# Top.net
KiCad netlist of a schematic drawn in Altium Designer
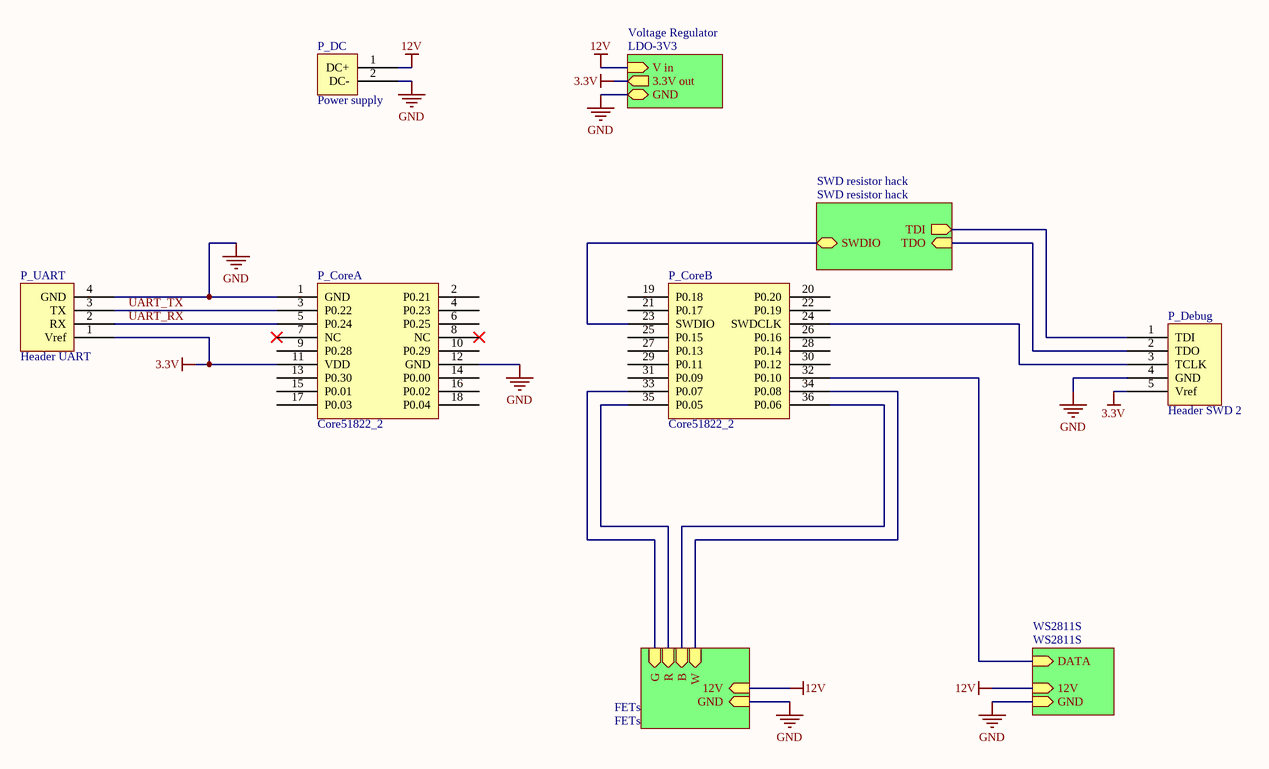
[diagram p0: Top.SchDoc]

(export (version "E")
  (design (tool "Eeschema 10.0.6"))
  (components
    (comp (ref "P_Core")
      (value "Core51822_2")
      (footprint "Core51822")
      (libsource (lib "Modules") (part "Core51822_2"))
    )
    (comp (ref "P_DC")
      (value "Power supply")
      (footprint "DC cable pad with holes")
      (libsource (lib "Core51822-related") (part "Power supply"))
    )
    (comp (ref "P_Debug")
      (value "Header SWD 2")
      (footprint "Header 1x5 2.54mm")
      (libsource (lib "Headers") (part "Header SWD 2"))
    )
    (comp (ref "P_UART")
      (value "Header UART")
      (footprint "Header 1x4 2.54mm")
      (libsource (lib "Core51822-related") (part "Header UART"))
    )
  )
  (nets
    (net (code "1") (name "/B") (class "Default")
      (node (ref "P_Core") (pin "36") (pinfunction "P0.06_36") (pintype "passive"))
    )
    (net (code "2") (name "/DATA") (class "Default")
      (node (ref "P_Core") (pin "32") (pinfunction "P0.10_32") (pintype "passive"))
    )
    (net (code "3") (name "/G") (class "Default")
      (node (ref "P_Core") (pin "33") (pinfunction "P0.07_33") (pintype "passive"))
    )
    (net (code "4") (name "/R") (class "Default")
      (node (ref "P_Core") (pin "35") (pinfunction "P0.05_35") (pintype "passive"))
    )
    (net (code "5") (name "/SWDIO") (class "Default")
      (node (ref "P_Core") (pin "23") (pinfunction "SWDIO_23") (pintype "passive"))
    )
    (net (code "6") (name "/TDI") (class "Default")
      (node (ref "P_Debug") (pin "1") (pinfunction "TDI_1") (pintype "passive"))
    )
    (net (code "7") (name "/TDO") (class "Default")
      (node (ref "P_Debug") (pin "2") (pinfunction "TDO_2") (pintype "passive"))
    )
    (net (code "8") (name "/UART_RX") (class "Default")
      (node (ref "P_Core") (pin "5") (pinfunction "P0.24_5") (pintype "passive"))
      (node (ref "P_UART") (pin "2") (pinfunction "RX_2") (pintype "passive"))
    )
    (net (code "9") (name "/UART_TX") (class "Default")
      (node (ref "P_Core") (pin "3") (pinfunction "P0.22_3") (pintype "power_in"))
      (node (ref "P_UART") (pin "3") (pinfunction "TX_3") (pintype "passive"))
    )
    (net (code "10") (name "/W") (class "Default")
      (node (ref "P_Core") (pin "34") (pinfunction "P0.08_34") (pintype "passive"))
    )
    (net (code "11") (name "3.3V") (class "Default")
      (node (ref "P_Core") (pin "11") (pinfunction "VDD_11") (pintype "passive"))
      (node (ref "P_Debug") (pin "5") (pinfunction "Vref_5") (pintype "passive"))
      (node (ref "P_UART") (pin "1") (pinfunction "Vref_1") (pintype "passive"))
    )
    (net (code "12") (name "12V") (class "Default")
      (node (ref "P_DC") (pin "1") (pinfunction "DC+_1") (pintype "passive"))
    )
    (net (code "13") (name "GND") (class "Default")
      (node (ref "P_Core") (pin "1") (pinfunction "GND_1") (pintype "passive"))
      (node (ref "P_Core") (pin "12") (pinfunction "GND_12") (pintype "passive"))
      (node (ref "P_DC") (pin "2") (pinfunction "DC-_2") (pintype "passive"))
      (node (ref "P_Debug") (pin "4") (pinfunction "GND_4") (pintype "passive"))
      (node (ref "P_UART") (pin "4") (pinfunction "GND_4") (pintype "passive"))
    )
    (net (code "14") (name "Net-(P_CoreB-SWDCLK)") (class "Default")
      (node (ref "P_Core") (pin "24") (pinfunction "SWDCLK_24") (pintype "passive"))
      (node (ref "P_Debug") (pin "3") (pinfunction "TCLK_3") (pintype "passive"))
    )
    (net (code "15") (name "unconnected-(P_CoreA-NC-Pad7)") (class "Default")
      (node (ref "P_Core") (pin "7") (pinfunction "NC_7") (pintype "passive+no_connect"))
    )
    (net (code "16") (name "unconnected-(P_CoreA-NC-Pad8)") (class "Default")
      (node (ref "P_Core") (pin "8") (pinfunction "NC_8") (pintype "passive+no_connect"))
    )
    (net (code "17") (name "unconnected-(P_CoreA-P0.00-Pad14)") (class "Default")
      (node (ref "P_Core") (pin "14") (pinfunction "P0.00_14") (pintype "passive"))
    )
    (net (code "18") (name "unconnected-(P_CoreA-P0.01-Pad15)") (class "Default")
      (node (ref "P_Core") (pin "15") (pinfunction "P0.01_15") (pintype "passive"))
    )
    (net (code "19") (name "unconnected-(P_CoreA-P0.02-Pad16)") (class "Default")
      (node (ref "P_Core") (pin "16") (pinfunction "P0.02_16") (pintype "passive"))
    )
    (net (code "20") (name "unconnected-(P_CoreA-P0.03-Pad17)") (class "Default")
      (node (ref "P_Core") (pin "17") (pinfunction "P0.03_17") (pintype "passive"))
    )
    (net (code "21") (name "unconnected-(P_CoreA-P0.04-Pad18)") (class "Default")
      (node (ref "P_Core") (pin "18") (pinfunction "P0.04_18") (pintype "passive"))
    )
    (net (code "22") (name "unconnected-(P_CoreA-P0.21-Pad2)") (class "Default")
      (node (ref "P_Core") (pin "2") (pinfunction "P0.21_2") (pintype "passive"))
    )
    (net (code "23") (name "unconnected-(P_CoreA-P0.23-Pad4)") (class "Default")
      (node (ref "P_Core") (pin "4") (pinfunction "P0.23_4") (pintype "passive"))
    )
    (net (code "24") (name "unconnected-(P_CoreA-P0.25-Pad6)") (class "Default")
      (node (ref "P_Core") (pin "6") (pinfunction "P0.25_6") (pintype "passive"))
    )
    (net (code "25") (name "unconnected-(P_CoreA-P0.28-Pad9)") (class "Default")
      (node (ref "P_Core") (pin "9") (pinfunction "P0.28_9") (pintype "passive"))
    )
    (net (code "26") (name "unconnected-(P_CoreA-P0.29-Pad10)") (class "Default")
      (node (ref "P_Core") (pin "10") (pinfunction "P0.29_10") (pintype "passive"))
    )
    (net (code "27") (name "unconnected-(P_CoreA-P0.30-Pad13)") (class "Default")
      (node (ref "P_Core") (pin "13") (pinfunction "P0.30_13") (pintype "passive"))
    )
    (net (code "28") (name "unconnected-(P_CoreB-P0.09-Pad31)") (class "Default")
      (node (ref "P_Core") (pin "31") (pinfunction "P0.09_31") (pintype "passive"))
    )
    (net (code "29") (name "unconnected-(P_CoreB-P0.11-Pad29)") (class "Default")
      (node (ref "P_Core") (pin "29") (pinfunction "P0.11_29") (pintype "passive"))
    )
    (net (code "30") (name "unconnected-(P_CoreB-P0.12-Pad30)") (class "Default")
      (node (ref "P_Core") (pin "30") (pinfunction "P0.12_30") (pintype "passive"))
    )
    (net (code "31") (name "unconnected-(P_CoreB-P0.13-Pad27)") (class "Default")
      (node (ref "P_Core") (pin "27") (pinfunction "P0.13_27") (pintype "passive"))
    )
    (net (code "32") (name "unconnected-(P_CoreB-P0.14-Pad28)") (class "Default")
      (node (ref "P_Core") (pin "28") (pinfunction "P0.14_28") (pintype "passive"))
    )
    (net (code "33") (name "unconnected-(P_CoreB-P0.15-Pad25)") (class "Default")
      (node (ref "P_Core") (pin "25") (pinfunction "P0.15_25") (pintype "passive"))
    )
    (net (code "34") (name "unconnected-(P_CoreB-P0.16-Pad26)") (class "Default")
      (node (ref "P_Core") (pin "26") (pinfunction "P0.16_26") (pintype "passive"))
    )
    (net (code "35") (name "unconnected-(P_CoreB-P0.17-Pad21)") (class "Default")
      (node (ref "P_Core") (pin "21") (pinfunction "P0.17_21") (pintype "power_in"))
    )
    (net (code "36") (name "unconnected-(P_CoreB-P0.18-Pad19)") (class "Default")
      (node (ref "P_Core") (pin "19") (pinfunction "P0.18_19") (pintype "passive"))
    )
    (net (code "37") (name "unconnected-(P_CoreB-P0.19-Pad22)") (class "Default")
      (node (ref "P_Core") (pin "22") (pinfunction "P0.19_22") (pintype "passive"))
    )
    (net (code "38") (name "unconnected-(P_CoreB-P0.20-Pad20)") (class "Default")
      (node (ref "P_Core") (pin "20") (pinfunction "P0.20_20") (pintype "passive"))
    )
  )
)
